# motorcontrol.net
KiCad netlist of a schematic drawn in EAGLE
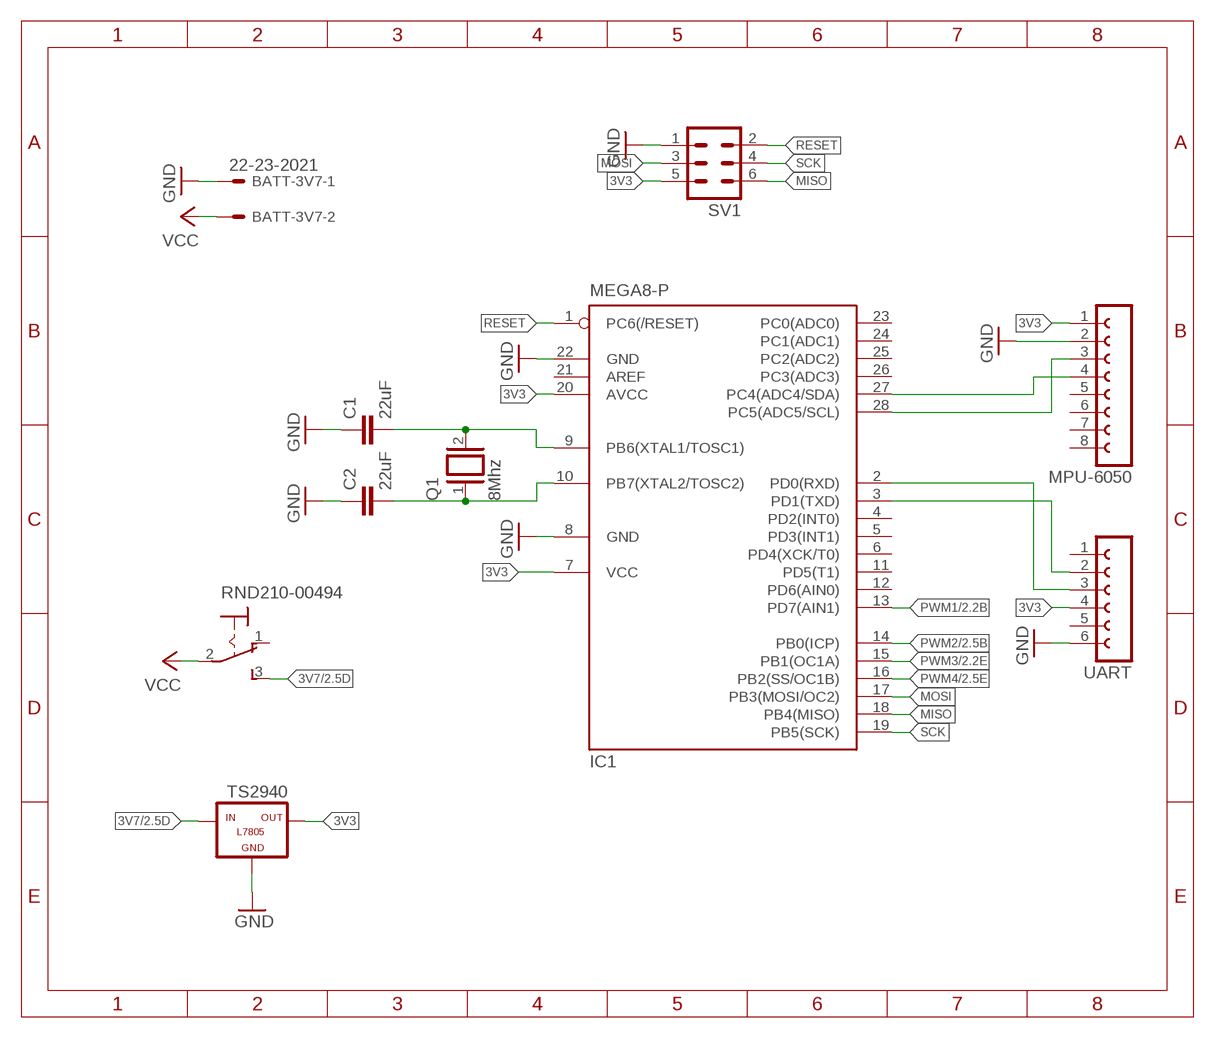
[diagram p0: schematic, sheet 1]
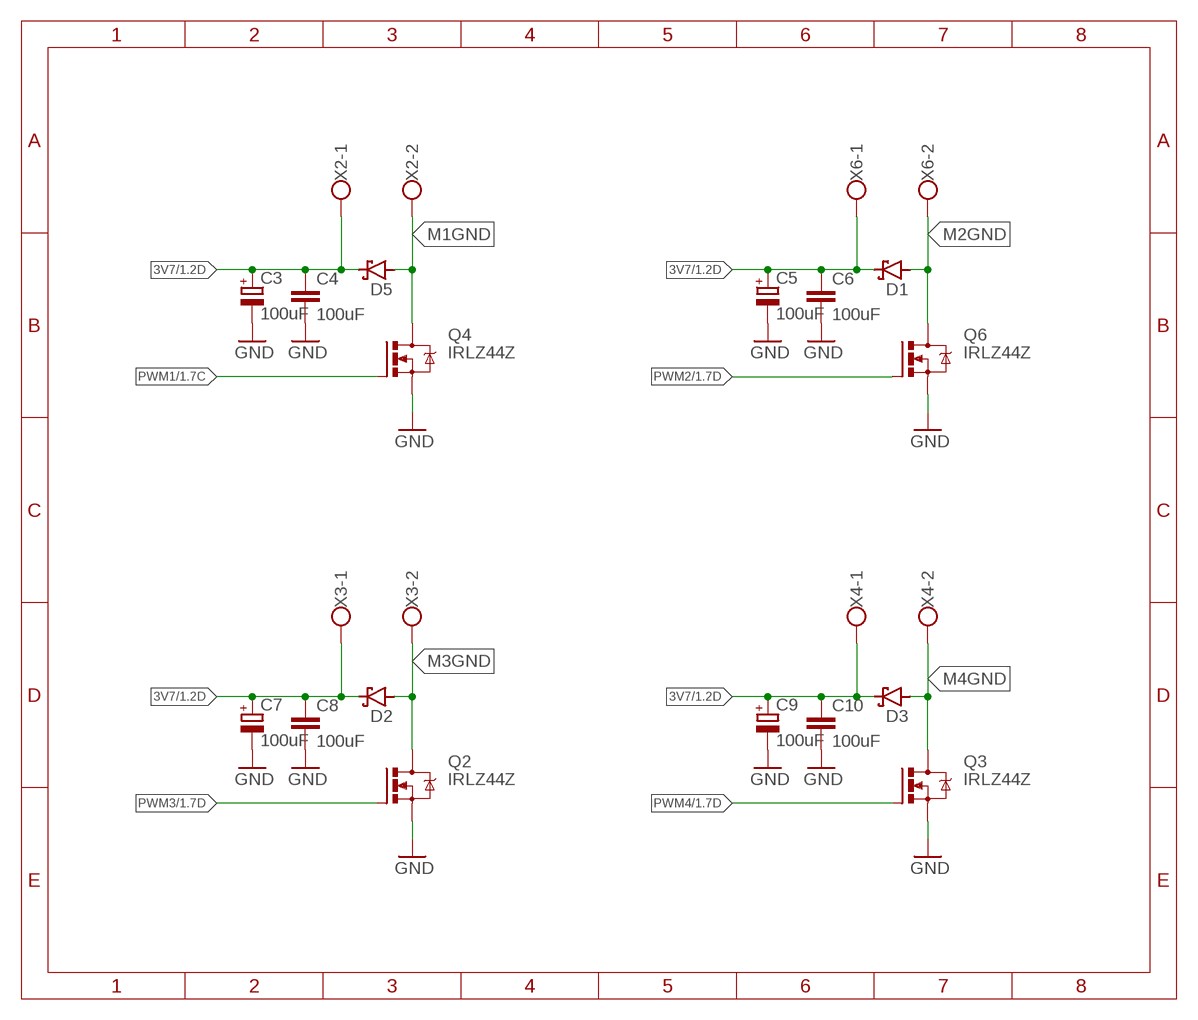
[diagram p1: schematic, sheet 2]

(export (version "E")
  (design (tool "Eeschema 10.0.6"))
  (components
    (comp (ref "C3")
      (value "100uF")
      (footprint "eagle-import:E2-5")
      (libsource (lib "eagle-import") (part "CPOL-EUE2-5"))
    )
    (comp (ref "C4")
      (value "100uF")
      (footprint "eagle-import:C025-025X050")
      (libsource (lib "eagle-import") (part "C-EU025-025X050"))
    )
    (comp (ref "C5")
      (value "100uF")
      (footprint "eagle-import:E2-5")
      (libsource (lib "eagle-import") (part "CPOL-EUE2-5"))
    )
    (comp (ref "C6")
      (value "100uF")
      (footprint "eagle-import:C025-025X050")
      (libsource (lib "eagle-import") (part "C-EU025-025X050"))
    )
    (comp (ref "C7")
      (value "100uF")
      (footprint "eagle-import:E2-5")
      (libsource (lib "eagle-import") (part "CPOL-EUE2-5"))
    )
    (comp (ref "C8")
      (value "100uF")
      (footprint "eagle-import:C025-025X050")
      (libsource (lib "eagle-import") (part "C-EU025-025X050"))
    )
    (comp (ref "C9")
      (value "100uF")
      (footprint "eagle-import:E2-5")
      (libsource (lib "eagle-import") (part "CPOL-EUE2-5"))
    )
    (comp (ref "C10")
      (value "100uF")
      (footprint "eagle-import:C025-025X050")
      (libsource (lib "eagle-import") (part "C-EU025-025X050"))
    )
    (comp (ref "D1")
      (value "SCHOTTKY-DIODEDO201T15")
      (footprint "eagle-import:DO201T15")
      (libsource (lib "eagle-import") (part "SCHOTTKY-DIODEDO201T15"))
    )
    (comp (ref "D2")
      (value "SCHOTTKY-DIODEDO201T15")
      (footprint "eagle-import:DO201T15")
      (libsource (lib "eagle-import") (part "SCHOTTKY-DIODEDO201T15"))
    )
    (comp (ref "D3")
      (value "SCHOTTKY-DIODEDO201T15")
      (footprint "eagle-import:DO201T15")
      (libsource (lib "eagle-import") (part "SCHOTTKY-DIODEDO201T15"))
    )
    (comp (ref "D5")
      (value "SCHOTTKY-DIODEDO201T15")
      (footprint "eagle-import:DO201T15")
      (libsource (lib "eagle-import") (part "SCHOTTKY-DIODEDO201T15"))
    )
    (comp (ref "Q2")
      (value "IRLZ44Z")
      (footprint "eagle-import:TO220BH")
      (libsource (lib "eagle-import") (part "IRLZ44Z"))
    )
    (comp (ref "Q3")
      (value "IRLZ44Z")
      (footprint "eagle-import:TO220BH")
      (libsource (lib "eagle-import") (part "IRLZ44Z"))
    )
    (comp (ref "Q4")
      (value "IRLZ44Z")
      (footprint "eagle-import:TO220BH")
      (libsource (lib "eagle-import") (part "IRLZ44Z"))
    )
    (comp (ref "Q6")
      (value "IRLZ44Z")
      (footprint "eagle-import:TO220BH")
      (libsource (lib "eagle-import") (part "IRLZ44Z"))
    )
    (comp (ref "X2")
      (value "W237-102")
      (footprint "eagle-import:W237-102")
      (fields (field (name "MPN") "237-102"))
      (libsource (lib "eagle-import") (part "W237-102"))
    )
    (comp (ref "X3")
      (value "W237-102")
      (footprint "eagle-import:W237-102")
      (fields (field (name "MPN") "237-102"))
      (libsource (lib "eagle-import") (part "W237-102"))
    )
    (comp (ref "X4")
      (value "W237-102")
      (footprint "eagle-import:W237-102")
      (fields (field (name "MPN") "237-102"))
      (libsource (lib "eagle-import") (part "W237-102"))
    )
    (comp (ref "X6")
      (value "W237-102")
      (footprint "eagle-import:W237-102")
      (fields (field (name "MPN") "237-102"))
      (libsource (lib "eagle-import") (part "W237-102"))
    )
    (comp (ref "BATT-3V7")
      (value "22-23-2021")
      (footprint "eagle-import:22-23-2021")
      (fields (field (name "MF") "MOLEX"))
      (libsource (lib "eagle-import") (part "22-23-2021"))
    )
    (comp (ref "C1")
      (value "22uF")
      (footprint "eagle-import:C025-025X050")
      (libsource (lib "eagle-import") (part "C-EU025-025X050"))
    )
    (comp (ref "C2")
      (value "22uF")
      (footprint "eagle-import:C025-025X050")
      (libsource (lib "eagle-import") (part "C-EU025-025X050"))
    )
    (comp (ref "IC1")
      (value "MEGA8-P")
      (footprint "eagle-import:DIL28-3")
      (libsource (lib "eagle-import") (part "MEGA8-P"))
    )
    (comp (ref "MPU-6050")
      (value "FE08-1")
      (footprint "eagle-import:FE08")
      (libsource (lib "eagle-import") (part "FE08-1"))
    )
    (comp (ref "Q1")
      (value "8Mhz")
      (footprint "eagle-import:QS")
      (libsource (lib "eagle-import") (part "XTAL/S"))
    )
    (comp (ref "RND210-00494")
      (value "320-916")
      (footprint "eagle-import:320-916")
      (libsource (lib "eagle-import") (part "320-916"))
    )
    (comp (ref "SV1")
      (value "MA03-2")
      (footprint "eagle-import:MA03-2")
      (libsource (lib "eagle-import") (part "MA03-2"))
    )
    (comp (ref "TS2940")
      (value "TS2940")
      (footprint "eagle-import:TO220")
      (libsource (lib "eagle-import") (part "TS2940"))
    )
    (comp (ref "UART")
      (value "FE06-1")
      (footprint "eagle-import:FE06")
      (libsource (lib "eagle-import") (part "FE06-1"))
    )
  )
  (nets
    (net (code "1") (name "3V3") (class "Default")
      (node (ref "IC1") (pin "20") (pinfunction "AVCC_20") (pintype "power_in"))
      (node (ref "IC1") (pin "7") (pinfunction "VCC_7") (pintype "power_in"))
      (node (ref "MPU-6050") (pin "1") (pinfunction "1_1") (pintype "passive"))
      (node (ref "SV1") (pin "5") (pinfunction "5_5") (pintype "passive"))
      (node (ref "TS2940") (pin "3") (pinfunction "OUT_3") (pintype "passive"))
      (node (ref "UART") (pin "4") (pinfunction "4_4") (pintype "passive"))
    )
    (net (code "2") (name "3V7") (class "Default")
      (node (ref "C10") (pin "1") (pinfunction "1_1") (pintype "passive"))
      (node (ref "C3") (pin "+") (pinfunction "+_+") (pintype "passive"))
      (node (ref "C4") (pin "1") (pinfunction "1_1") (pintype "passive"))
      (node (ref "C5") (pin "+") (pinfunction "+_+") (pintype "passive"))
      (node (ref "C6") (pin "1") (pinfunction "1_1") (pintype "passive"))
      (node (ref "C7") (pin "+") (pinfunction "+_+") (pintype "passive"))
      (node (ref "C8") (pin "1") (pinfunction "1_1") (pintype "passive"))
      (node (ref "C9") (pin "+") (pinfunction "+_+") (pintype "passive"))
      (node (ref "D1") (pin "C") (pinfunction "C_C") (pintype "passive"))
      (node (ref "D2") (pin "C") (pinfunction "C_C") (pintype "passive"))
      (node (ref "D3") (pin "C") (pinfunction "C_C") (pintype "passive"))
      (node (ref "D5") (pin "C") (pinfunction "C_C") (pintype "passive"))
      (node (ref "RND210-00494") (pin "3") (pinfunction "S_3") (pintype "passive"))
      (node (ref "TS2940") (pin "1") (pinfunction "IN_1") (pintype "input"))
      (node (ref "X2") (pin "1") (pinfunction "KL_1") (pintype "passive"))
      (node (ref "X3") (pin "1") (pinfunction "KL_1") (pintype "passive"))
      (node (ref "X4") (pin "1") (pinfunction "KL_1") (pintype "passive"))
      (node (ref "X6") (pin "1") (pinfunction "KL_1") (pintype "passive"))
    )
    (net (code "3") (name "GND") (class "Default")
      (node (ref "BATT-3V7") (pin "1") (pinfunction "S_1") (pintype "passive"))
      (node (ref "C1") (pin "1") (pinfunction "1_1") (pintype "passive"))
      (node (ref "C10") (pin "2") (pinfunction "2_2") (pintype "passive"))
      (node (ref "C2") (pin "1") (pinfunction "1_1") (pintype "passive"))
      (node (ref "C3") (pin "-") (pinfunction "-_-") (pintype "passive"))
      (node (ref "C4") (pin "2") (pinfunction "2_2") (pintype "passive"))
      (node (ref "C5") (pin "-") (pinfunction "-_-") (pintype "passive"))
      (node (ref "C6") (pin "2") (pinfunction "2_2") (pintype "passive"))
      (node (ref "C7") (pin "-") (pinfunction "-_-") (pintype "passive"))
      (node (ref "C8") (pin "2") (pinfunction "2_2") (pintype "passive"))
      (node (ref "C9") (pin "-") (pinfunction "-_-") (pintype "passive"))
      (node (ref "IC1") (pin "22") (pinfunction "GND_22") (pintype "power_in"))
      (node (ref "IC1") (pin "8") (pinfunction "GND_8") (pintype "power_in"))
      (node (ref "MPU-6050") (pin "2") (pinfunction "2_2") (pintype "passive"))
      (node (ref "Q2") (pin "S") (pinfunction "S_S") (pintype "passive"))
      (node (ref "Q3") (pin "S") (pinfunction "S_S") (pintype "passive"))
      (node (ref "Q4") (pin "S") (pinfunction "S_S") (pintype "passive"))
      (node (ref "Q6") (pin "S") (pinfunction "S_S") (pintype "passive"))
      (node (ref "SV1") (pin "1") (pinfunction "1_1") (pintype "passive"))
      (node (ref "TS2940") (pin "2") (pinfunction "GND_2") (pintype "input"))
      (node (ref "UART") (pin "6") (pinfunction "6_6") (pintype "passive"))
    )
    (net (code "4") (name "M1GND") (class "Default")
      (node (ref "D5") (pin "A") (pinfunction "A_A") (pintype "passive"))
      (node (ref "Q4") (pin "D") (pinfunction "D_D") (pintype "passive"))
      (node (ref "X2") (pin "2") (pinfunction "KL_2") (pintype "passive"))
    )
    (net (code "5") (name "M2GND") (class "Default")
      (node (ref "D1") (pin "A") (pinfunction "A_A") (pintype "passive"))
      (node (ref "Q6") (pin "D") (pinfunction "D_D") (pintype "passive"))
      (node (ref "X6") (pin "2") (pinfunction "KL_2") (pintype "passive"))
    )
    (net (code "6") (name "M3GND") (class "Default")
      (node (ref "D2") (pin "A") (pinfunction "A_A") (pintype "passive"))
      (node (ref "Q2") (pin "D") (pinfunction "D_D") (pintype "passive"))
      (node (ref "X3") (pin "2") (pinfunction "KL_2") (pintype "passive"))
    )
    (net (code "7") (name "M4GND") (class "Default")
      (node (ref "D3") (pin "A") (pinfunction "A_A") (pintype "passive"))
      (node (ref "Q3") (pin "D") (pinfunction "D_D") (pintype "passive"))
      (node (ref "X4") (pin "2") (pinfunction "KL_2") (pintype "passive"))
    )
    (net (code "8") (name "MISO") (class "Default")
      (node (ref "IC1") (pin "18") (pinfunction "PB4(MISO)_18") (pintype "bidirectional"))
      (node (ref "SV1") (pin "6") (pinfunction "6_6") (pintype "passive"))
    )
    (net (code "9") (name "MOSI") (class "Default")
      (node (ref "IC1") (pin "17") (pinfunction "PB3(MOSI/OC2)_17") (pintype "bidirectional"))
      (node (ref "SV1") (pin "3") (pinfunction "3_3") (pintype "passive"))
    )
    (net (code "10") (name "Net-(IC1-PB6(XTAL1{slash}TOSC1))") (class "Default")
      (node (ref "C1") (pin "2") (pinfunction "2_2") (pintype "passive"))
      (node (ref "IC1") (pin "9") (pinfunction "PB6(XTAL1/TOSC1)_9") (pintype "bidirectional"))
      (node (ref "Q1") (pin "2") (pinfunction "2_2") (pintype "passive"))
    )
    (net (code "11") (name "Net-(IC1-PB7(XTAL2{slash}TOSC2))") (class "Default")
      (node (ref "C2") (pin "2") (pinfunction "2_2") (pintype "passive"))
      (node (ref "IC1") (pin "10") (pinfunction "PB7(XTAL2/TOSC2)_10") (pintype "bidirectional"))
      (node (ref "Q1") (pin "1") (pinfunction "1_1") (pintype "passive"))
    )
    (net (code "12") (name "Net-(IC1-PC4(ADC4{slash}SDA))") (class "Default")
      (node (ref "IC1") (pin "27") (pinfunction "PC4(ADC4/SDA)_27") (pintype "bidirectional"))
      (node (ref "MPU-6050") (pin "4") (pinfunction "4_4") (pintype "passive"))
    )
    (net (code "13") (name "Net-(IC1-PC5(ADC5{slash}SCL))") (class "Default")
      (node (ref "IC1") (pin "28") (pinfunction "PC5(ADC5/SCL)_28") (pintype "bidirectional"))
      (node (ref "MPU-6050") (pin "3") (pinfunction "3_3") (pintype "passive"))
    )
    (net (code "14") (name "Net-(IC1-PD0(RXD))") (class "Default")
      (node (ref "IC1") (pin "2") (pinfunction "PD0(RXD)_2") (pintype "bidirectional"))
      (node (ref "UART") (pin "3") (pinfunction "3_3") (pintype "passive"))
    )
    (net (code "15") (name "Net-(IC1-PD1(TXD))") (class "Default")
      (node (ref "IC1") (pin "3") (pinfunction "PD1(TXD)_3") (pintype "bidirectional"))
      (node (ref "UART") (pin "2") (pinfunction "2_2") (pintype "passive"))
    )
    (net (code "16") (name "PWM1") (class "Default")
      (node (ref "IC1") (pin "13") (pinfunction "PD7(AIN1)_13") (pintype "bidirectional"))
      (node (ref "Q4") (pin "G") (pinfunction "G_G") (pintype "passive"))
    )
    (net (code "17") (name "PWM2") (class "Default")
      (node (ref "IC1") (pin "14") (pinfunction "PB0(ICP)_14") (pintype "bidirectional"))
      (node (ref "Q6") (pin "G") (pinfunction "G_G") (pintype "passive"))
    )
    (net (code "18") (name "PWM3") (class "Default")
      (node (ref "IC1") (pin "15") (pinfunction "PB1(OC1A)_15") (pintype "bidirectional"))
      (node (ref "Q2") (pin "G") (pinfunction "G_G") (pintype "passive"))
    )
    (net (code "19") (name "PWM4") (class "Default")
      (node (ref "IC1") (pin "16") (pinfunction "PB2(SS/OC1B)_16") (pintype "bidirectional"))
      (node (ref "Q3") (pin "G") (pinfunction "G_G") (pintype "passive"))
    )
    (net (code "20") (name "RESET") (class "Default")
      (node (ref "IC1") (pin "1") (pinfunction "PC6(/RESET)_1") (pintype "bidirectional"))
      (node (ref "SV1") (pin "2") (pinfunction "2_2") (pintype "passive"))
    )
    (net (code "21") (name "SCK") (class "Default")
      (node (ref "IC1") (pin "19") (pinfunction "PB5(SCK)_19") (pintype "bidirectional"))
      (node (ref "SV1") (pin "4") (pinfunction "4_4") (pintype "passive"))
    )
    (net (code "22") (name "VCC") (class "Default")
      (node (ref "BATT-3V7") (pin "2") (pinfunction "S_2") (pintype "passive"))
      (node (ref "RND210-00494") (pin "2") (pinfunction "P_2") (pintype "passive"))
    )
    (net (code "23") (name "unconnected-(IC1-AREF-Pad21)") (class "Default")
      (node (ref "IC1") (pin "21") (pinfunction "AREF_21") (pintype "passive"))
    )
    (net (code "24") (name "unconnected-(IC1-PC0(ADC0)-Pad23)") (class "Default")
      (node (ref "IC1") (pin "23") (pinfunction "PC0(ADC0)_23") (pintype "bidirectional"))
    )
    (net (code "25") (name "unconnected-(IC1-PC1(ADC1)-Pad24)") (class "Default")
      (node (ref "IC1") (pin "24") (pinfunction "PC1(ADC1)_24") (pintype "bidirectional"))
    )
    (net (code "26") (name "unconnected-(IC1-PC2(ADC2)-Pad25)") (class "Default")
      (node (ref "IC1") (pin "25") (pinfunction "PC2(ADC2)_25") (pintype "bidirectional"))
    )
    (net (code "27") (name "unconnected-(IC1-PC3(ADC3)-Pad26)") (class "Default")
      (node (ref "IC1") (pin "26") (pinfunction "PC3(ADC3)_26") (pintype "bidirectional"))
    )
    (net (code "28") (name "unconnected-(IC1-PD2(INT0)-Pad4)") (class "Default")
      (node (ref "IC1") (pin "4") (pinfunction "PD2(INT0)_4") (pintype "bidirectional"))
    )
    (net (code "29") (name "unconnected-(IC1-PD3(INT1)-Pad5)") (class "Default")
      (node (ref "IC1") (pin "5") (pinfunction "PD3(INT1)_5") (pintype "bidirectional"))
    )
    (net (code "30") (name "unconnected-(IC1-PD4(XCK{slash}T0)-Pad6)") (class "Default")
      (node (ref "IC1") (pin "6") (pinfunction "PD4(XCK/T0)_6") (pintype "bidirectional"))
    )
    (net (code "31") (name "unconnected-(IC1-PD5(T1)-Pad11)") (class "Default")
      (node (ref "IC1") (pin "11") (pinfunction "PD5(T1)_11") (pintype "bidirectional"))
    )
    (net (code "32") (name "unconnected-(IC1-PD6(AIN0)-Pad12)") (class "Default")
      (node (ref "IC1") (pin "12") (pinfunction "PD6(AIN0)_12") (pintype "bidirectional"))
    )
    (net (code "33") (name "unconnected-(MPU-6050-Pad5)") (class "Default")
      (node (ref "MPU-6050") (pin "5") (pinfunction "5_5") (pintype "passive"))
    )
    (net (code "34") (name "unconnected-(MPU-6050-Pad6)") (class "Default")
      (node (ref "MPU-6050") (pin "6") (pinfunction "6_6") (pintype "passive"))
    )
    (net (code "35") (name "unconnected-(MPU-6050-Pad7)") (class "Default")
      (node (ref "MPU-6050") (pin "7") (pinfunction "7_7") (pintype "passive"))
    )
    (net (code "36") (name "unconnected-(MPU-6050-Pad8)") (class "Default")
      (node (ref "MPU-6050") (pin "8") (pinfunction "8_8") (pintype "passive"))
    )
    (net (code "37") (name "unconnected-(RND210-00494-O-Pad1)") (class "Default")
      (node (ref "RND210-00494") (pin "1") (pinfunction "O_1") (pintype "passive"))
    )
    (net (code "38") (name "unconnected-(UART-Pad1)") (class "Default")
      (node (ref "UART") (pin "1") (pinfunction "1_1") (pintype "passive"))
    )
    (net (code "39") (name "unconnected-(UART-Pad5)") (class "Default")
      (node (ref "UART") (pin "5") (pinfunction "5_5") (pintype "passive"))
    )
  )
)
